# ATtiny_programmer.net
KiCad netlist of a schematic drawn in EAGLE
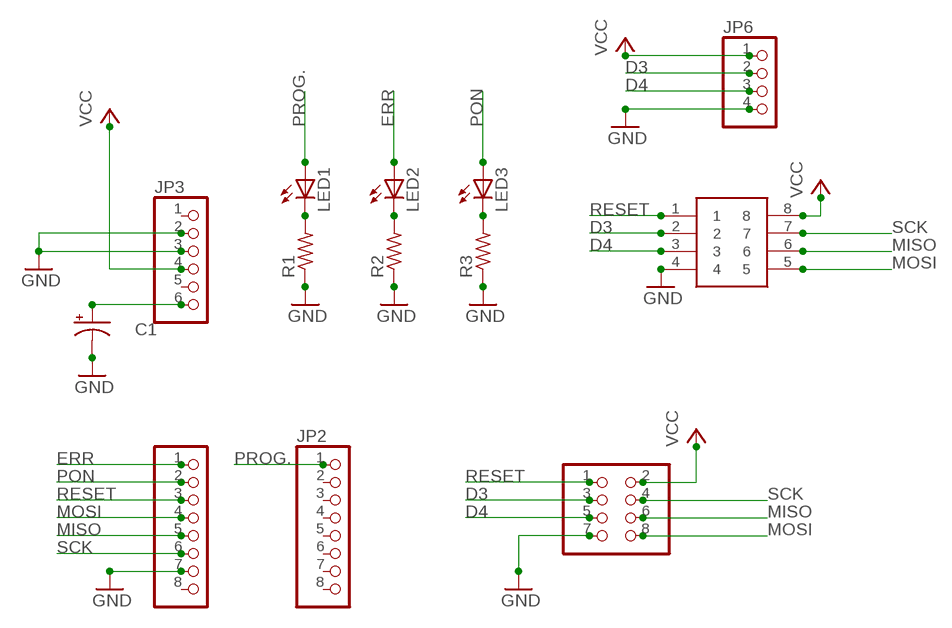
[diagram p0: schematic, sheet 1]

(export (version "E")
  (design (tool "Eeschema 10.0.6"))
  (components
    (comp (ref "C1")
      (value "CPOL-USE5-6")
      (footprint "eagle-import:E5-6")
      (libsource (lib "eagle-import") (part "CPOL-USE5-6"))
    )
    (comp (ref "IC1")
      (value "1-2199298-2")
      (footprint "eagle-import:DIPS762W70P254L1016H510Q8N")
      (fields (field (name "MOUSER_PART_NUMBER") "571-1-2199298-2"))
      (libsource (lib "eagle-import") (part "1-2199298-2"))
    )
    (comp (ref "JP1")
      (value "PINHD-2X4")
      (footprint "eagle-import:2X04")
      (libsource (lib "eagle-import") (part "PINHD-2X4"))
    )
    (comp (ref "JP2")
      (value "PINHD-1X8")
      (footprint "eagle-import:1X08")
      (libsource (lib "eagle-import") (part "PINHD-1X8"))
    )
    (comp (ref "JP3")
      (value "PINHD-1X6")
      (footprint "eagle-import:1X06")
      (libsource (lib "eagle-import") (part "PINHD-1X6"))
    )
    (comp (ref "JP4")
      (value "PINHD-1X8")
      (footprint "eagle-import:1X08")
      (libsource (lib "eagle-import") (part "PINHD-1X8"))
    )
    (comp (ref "JP6")
      (value "PINHD-1X4")
      (footprint "eagle-import:1X04")
      (libsource (lib "eagle-import") (part "PINHD-1X4"))
    )
    (comp (ref "LED1")
      (value "LED3MM")
      (footprint "eagle-import:LED3MM")
      (libsource (lib "eagle-import") (part "LED3MM"))
    )
    (comp (ref "LED2")
      (value "LED3MM")
      (footprint "eagle-import:LED3MM")
      (libsource (lib "eagle-import") (part "LED3MM"))
    )
    (comp (ref "LED3")
      (value "LED3MM")
      (footprint "eagle-import:LED3MM")
      (libsource (lib "eagle-import") (part "adafruit_420_LED3MM"))
    )
    (comp (ref "R1")
      (value "R-US_0207/10")
      (footprint "eagle-import:0207_10")
      (libsource (lib "eagle-import") (part "R-US_0207/10"))
    )
    (comp (ref "R2")
      (value "R-US_0207/10")
      (footprint "eagle-import:0207_10")
      (libsource (lib "eagle-import") (part "R-US_0207/10"))
    )
    (comp (ref "R3")
      (value "R-US_0207/10")
      (footprint "eagle-import:0207_10")
      (libsource (lib "eagle-import") (part "R-US_0207/10"))
    )
  )
  (nets
    (net (code "1") (name "/D3") (class "Default")
      (node (ref "IC1") (pin "2") (pinfunction "2_2") (pintype "bidirectional"))
      (node (ref "JP1") (pin "3") (pinfunction "3_3") (pintype "passive"))
      (node (ref "JP6") (pin "2") (pinfunction "2_2") (pintype "passive"))
    )
    (net (code "2") (name "/D4") (class "Default")
      (node (ref "IC1") (pin "3") (pinfunction "3_3") (pintype "bidirectional"))
      (node (ref "JP1") (pin "5") (pinfunction "5_5") (pintype "passive"))
      (node (ref "JP6") (pin "3") (pinfunction "3_3") (pintype "passive"))
    )
    (net (code "3") (name "/ERR") (class "Default")
      (node (ref "JP4") (pin "1") (pinfunction "1_1") (pintype "passive"))
      (node (ref "LED2") (pin "A") (pinfunction "A_A") (pintype "passive"))
    )
    (net (code "4") (name "/MISO") (class "Default")
      (node (ref "IC1") (pin "6") (pinfunction "6_6") (pintype "bidirectional"))
      (node (ref "JP1") (pin "6") (pinfunction "6_6") (pintype "passive"))
      (node (ref "JP4") (pin "5") (pinfunction "5_5") (pintype "passive"))
    )
    (net (code "5") (name "/MOSI") (class "Default")
      (node (ref "IC1") (pin "5") (pinfunction "5_5") (pintype "bidirectional"))
      (node (ref "JP1") (pin "8") (pinfunction "8_8") (pintype "passive"))
      (node (ref "JP4") (pin "4") (pinfunction "4_4") (pintype "passive"))
    )
    (net (code "6") (name "/PON") (class "Default")
      (node (ref "JP4") (pin "2") (pinfunction "2_2") (pintype "passive"))
      (node (ref "LED3") (pin "A") (pinfunction "A_A") (pintype "passive"))
    )
    (net (code "7") (name "/PROG.") (class "Default")
      (node (ref "JP2") (pin "1") (pinfunction "1_1") (pintype "passive"))
      (node (ref "LED1") (pin "A") (pinfunction "A_A") (pintype "passive"))
    )
    (net (code "8") (name "/RESET") (class "Default")
      (node (ref "IC1") (pin "1") (pinfunction "1_1") (pintype "bidirectional"))
      (node (ref "JP1") (pin "1") (pinfunction "1_1") (pintype "passive"))
      (node (ref "JP4") (pin "3") (pinfunction "3_3") (pintype "passive"))
    )
    (net (code "9") (name "/SCK") (class "Default")
      (node (ref "IC1") (pin "7") (pinfunction "7_7") (pintype "bidirectional"))
      (node (ref "JP1") (pin "4") (pinfunction "4_4") (pintype "passive"))
      (node (ref "JP4") (pin "6") (pinfunction "6_6") (pintype "passive"))
    )
    (net (code "10") (name "GND") (class "Default")
      (node (ref "C1") (pin "-") (pinfunction "-_-") (pintype "passive"))
      (node (ref "IC1") (pin "4") (pinfunction "4_4") (pintype "bidirectional"))
      (node (ref "JP1") (pin "7") (pinfunction "7_7") (pintype "passive"))
      (node (ref "JP3") (pin "2") (pinfunction "2_2") (pintype "passive"))
      (node (ref "JP3") (pin "3") (pinfunction "3_3") (pintype "passive"))
      (node (ref "JP4") (pin "7") (pinfunction "7_7") (pintype "passive"))
      (node (ref "JP6") (pin "4") (pinfunction "4_4") (pintype "passive"))
      (node (ref "R1") (pin "1") (pinfunction "1_1") (pintype "passive"))
      (node (ref "R2") (pin "1") (pinfunction "1_1") (pintype "passive"))
      (node (ref "R3") (pin "1") (pinfunction "1_1") (pintype "passive"))
    )
    (net (code "11") (name "Net-(C1-Pad+)") (class "Default")
      (node (ref "C1") (pin "+") (pinfunction "+_+") (pintype "passive"))
      (node (ref "JP3") (pin "6") (pinfunction "6_6") (pintype "passive"))
    )
    (net (code "12") (name "Net-(LED1-C)") (class "Default")
      (node (ref "LED1") (pin "K") (pinfunction "C_K") (pintype "passive"))
      (node (ref "R1") (pin "2") (pinfunction "2_2") (pintype "passive"))
    )
    (net (code "13") (name "Net-(LED2-C)") (class "Default")
      (node (ref "LED2") (pin "K") (pinfunction "C_K") (pintype "passive"))
      (node (ref "R2") (pin "2") (pinfunction "2_2") (pintype "passive"))
    )
    (net (code "14") (name "Net-(LED3-C)") (class "Default")
      (node (ref "LED3") (pin "K") (pinfunction "C_K") (pintype "passive"))
      (node (ref "R3") (pin "2") (pinfunction "2_2") (pintype "passive"))
    )
    (net (code "15") (name "VCC") (class "Default")
      (node (ref "IC1") (pin "8") (pinfunction "8_8") (pintype "bidirectional"))
      (node (ref "JP1") (pin "2") (pinfunction "2_2") (pintype "passive"))
      (node (ref "JP3") (pin "4") (pinfunction "4_4") (pintype "passive"))
      (node (ref "JP6") (pin "1") (pinfunction "1_1") (pintype "passive"))
    )
    (net (code "16") (name "unconnected-(JP2-Pad2)") (class "Default")
      (node (ref "JP2") (pin "2") (pinfunction "2_2") (pintype "passive"))
    )
    (net (code "17") (name "unconnected-(JP2-Pad3)") (class "Default")
      (node (ref "JP2") (pin "3") (pinfunction "3_3") (pintype "passive"))
    )
    (net (code "18") (name "unconnected-(JP2-Pad4)") (class "Default")
      (node (ref "JP2") (pin "4") (pinfunction "4_4") (pintype "passive"))
    )
    (net (code "19") (name "unconnected-(JP2-Pad5)") (class "Default")
      (node (ref "JP2") (pin "5") (pinfunction "5_5") (pintype "passive"))
    )
    (net (code "20") (name "unconnected-(JP2-Pad6)") (class "Default")
      (node (ref "JP2") (pin "6") (pinfunction "6_6") (pintype "passive"))
    )
    (net (code "21") (name "unconnected-(JP2-Pad7)") (class "Default")
      (node (ref "JP2") (pin "7") (pinfunction "7_7") (pintype "passive"))
    )
    (net (code "22") (name "unconnected-(JP2-Pad8)") (class "Default")
      (node (ref "JP2") (pin "8") (pinfunction "8_8") (pintype "passive"))
    )
    (net (code "23") (name "unconnected-(JP3-Pad1)") (class "Default")
      (node (ref "JP3") (pin "1") (pinfunction "1_1") (pintype "passive"))
    )
    (net (code "24") (name "unconnected-(JP3-Pad5)") (class "Default")
      (node (ref "JP3") (pin "5") (pinfunction "5_5") (pintype "passive"))
    )
    (net (code "25") (name "unconnected-(JP4-Pad8)") (class "Default")
      (node (ref "JP4") (pin "8") (pinfunction "8_8") (pintype "passive"))
    )
  )
)
